# ESP-OLED.net
KiCad netlist of a schematic drawn in Altium Designer
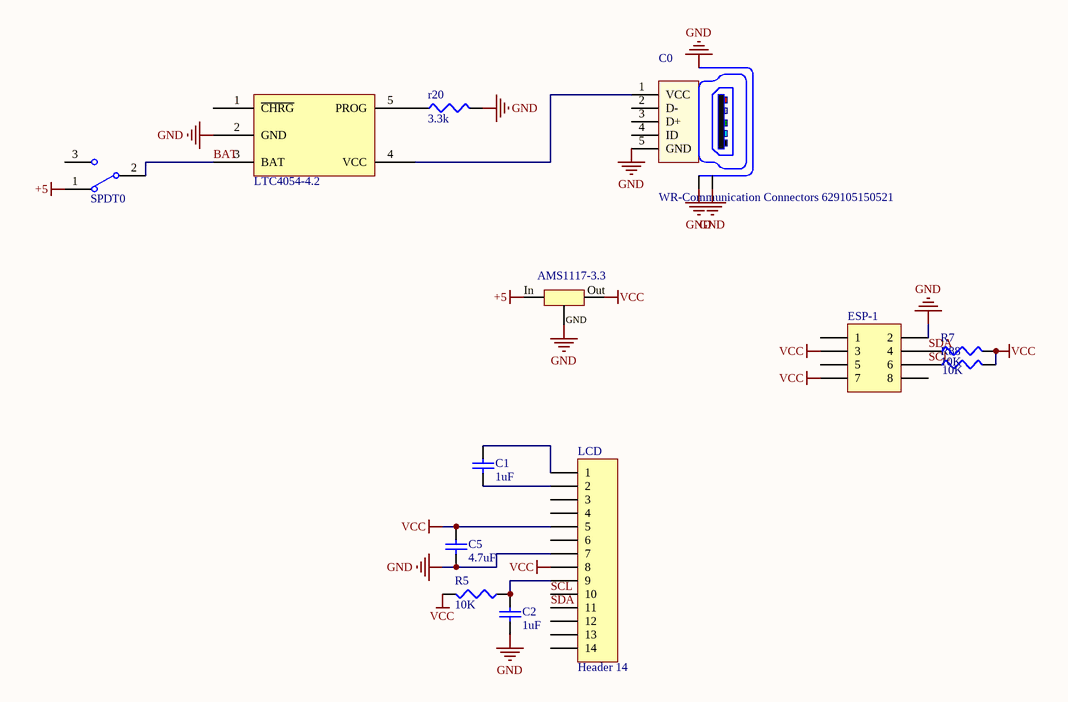
[diagram p0: ESP-OLED.SchDoc]

(export (version "E")
  (design (tool "Eeschema 10.0.6"))
  (components
    (comp (ref "ads") (value "LTC4054-4.2") (footprint "S5") (libsource (lib "arad") (part "LTC4054-4.2")))
    (comp (ref "C0")
      (value "WR-Communication Connectors 629105150521")
      (footprint "arad:629105150521_no_fixtures")
      (description "WR-COM_USB_Micro Type B_Horizontal_SMT")
      (fields
        (field (name "MANUFACTURER") "Würth Elektronik eiSos GmbH")
        (field (name "PARTNO") "629105150521")
        (field (name "CREATED BY") "Karrer Zheng")
      )
      (libsource (lib "arad") (part "WR-Communication Connectors 629105150521"))
    )
    (comp (ref "C1")
      (value "1uF")
      (footprint "1608[0603]")
      (description "Capacitor (Semiconductor SIM Model)")
      (fields (field (name "Comment") "Cap Semi") (field (name "PUBLISHER") "Altium Limited"))
      (libsource (lib "Miscellaneous Devices") (part "Cap Semi"))
    )
    (comp (ref "C2")
      (value "1uF")
      (footprint "1608[0603]")
      (description "Capacitor (Semiconductor SIM Model)")
      (fields (field (name "Comment") "Cap Semi") (field (name "PUBLISHER") "Altium Limited"))
      (libsource (lib "Miscellaneous Devices") (part "Cap Semi"))
    )
    (comp (ref "C5")
      (value "4.7uF")
      (footprint "1608[0603]")
      (description "Capacitor (Semiconductor SIM Model)")
      (fields (field (name "Comment") "Cap Semi") (field (name "PUBLISHER") "Altium Limited"))
      (libsource (lib "Miscellaneous Devices") (part "Cap Semi"))
    )
    (comp (ref "ESP-1")
      (value "Header 4X2")
      (footprint "ESP-01")
      (description "Header, 4-Pin, Dual row")
      (fields (field (name "PUBLISHER") "Altium Limited"))
      (libsource (lib "Miscellaneous Connectors") (part "Header 4X2"))
    )
    (comp (ref "LCD")
      (value "Header 14")
      (footprint "oled0.91")
      (description "Header, 14-Pin")
      (fields (field (name "PUBLISHER") "Altium Limited"))
      (libsource (lib "Miscellaneous Connectors") (part "Header 14"))
    )
    (comp (ref "R5")
      (value "10K")
      (footprint "J1-0603")
      (description "Resistor")
      (fields (field (name "Comment") "Res3") (field (name "PUBLISHER") "Altium Limited"))
      (libsource (lib "Miscellaneous Devices") (part "Res3"))
    )
    (comp (ref "R7")
      (value "10K")
      (footprint "J1-0603")
      (description "Resistor")
      (fields (field (name "Comment") "Res3") (field (name "PUBLISHER") "Altium Limited"))
      (libsource (lib "Miscellaneous Devices") (part "Res3"))
    )
    (comp (ref "r20")
      (value "3.3k")
      (footprint "J1-0603")
      (description "Resistor")
      (fields (field (name "Comment") "Res3") (field (name "PUBLISHER") "Altium Limited"))
      (libsource (lib "Miscellaneous Devices") (part "Res3"))
    )
    (comp (ref "R88")
      (value "10K")
      (footprint "J1-0603")
      (description "Resistor")
      (fields (field (name "Comment") "Res3") (field (name "PUBLISHER") "Altium Limited"))
      (libsource (lib "Miscellaneous Devices") (part "Res3"))
    )
    (comp (ref "reg")
      (value "AMS1117-3.3")
      (footprint "SOT223")
      (libsource (lib "Diverse") (part "AMS1117-3.3"))
    )
    (comp (ref "SPDT0")
      (value "450404015514")
      (footprint "450404015514")
      (description "WS-SLSU Mini SMT Slide Switch, Same Side Connection, Right Angled, SPDT")
      (fields (field (name "PUBLISHER") "Wurth Elektronik"))
      (libsource (lib "arad") (part "450404015514"))
    )
  )
  (nets
    (net (code "1") (name "+5") (class "Default")
      (node (ref "SPDT0") (pin "1") (pinfunction "1_1") (pintype "passive"))
      (node (ref "reg") (pin "3") (pinfunction "3_3") (pintype "passive"))
    )
    (net (code "2") (name "/BAT") (class "Default")
      (node (ref "SPDT0") (pin "2") (pinfunction "COM_2") (pintype "passive"))
      (node (ref "ads") (pin "3") (pinfunction "BAT_3") (pintype "passive"))
    )
    (net (code "3") (name "/SCL") (class "Default")
      (node (ref "ESP-1") (pin "6") (pinfunction "6_6") (pintype "passive"))
      (node (ref "LCD") (pin "10") (pinfunction "10_10") (pintype "passive"))
      (node (ref "R88") (pin "1") (pinfunction "1_1") (pintype "passive"))
    )
    (net (code "4") (name "/SDA") (class "Default")
      (node (ref "ESP-1") (pin "4") (pinfunction "4_4") (pintype "passive"))
      (node (ref "LCD") (pin "11") (pinfunction "11_11") (pintype "passive"))
      (node (ref "R7") (pin "1") (pinfunction "1_1") (pintype "passive"))
    )
    (net (code "5") (name "GND") (class "Default")
      (node (ref "C0") (pin "5") (pinfunction "GND_5") (pintype "passive"))
      (node (ref "C0") (pin "Z1") (pinfunction "Shield_Z1") (pintype "passive"))
      (node (ref "C0") (pin "Z2") (pinfunction "Shield_Z2") (pintype "passive"))
      (node (ref "C2") (pin "1") (pinfunction "1_1") (pintype "passive"))
      (node (ref "C5") (pin "1") (pinfunction "1_1") (pintype "passive"))
      (node (ref "ESP-1") (pin "2") (pinfunction "2_2") (pintype "passive"))
      (node (ref "LCD") (pin "7") (pinfunction "7_7") (pintype "passive"))
      (node (ref "ads") (pin "2") (pinfunction "GND_2") (pintype "passive"))
      (node (ref "r20") (pin "2") (pinfunction "2_2") (pintype "passive"))
      (node (ref "reg") (pin "1") (pinfunction "1_1") (pintype "passive"))
    )
    (net (code "6") (name "Net-(C0-VCC)") (class "Default")
      (node (ref "C0") (pin "1") (pinfunction "VCC_1") (pintype "passive"))
      (node (ref "ads") (pin "4") (pinfunction "VCC_4") (pintype "passive"))
    )
    (net (code "7") (name "Net-(C1-Pad1)") (class "Default")
      (node (ref "C1") (pin "1") (pinfunction "1_1") (pintype "passive"))
      (node (ref "LCD") (pin "2") (pinfunction "2_2") (pintype "passive"))
    )
    (net (code "8") (name "Net-(C1-Pad2)") (class "Default")
      (node (ref "C1") (pin "2") (pinfunction "2_2") (pintype "passive"))
      (node (ref "LCD") (pin "1") (pinfunction "1_1") (pintype "passive"))
    )
    (net (code "9") (name "Net-(C2-Pad2)") (class "Default")
      (node (ref "C2") (pin "2") (pinfunction "2_2") (pintype "passive"))
      (node (ref "LCD") (pin "9") (pinfunction "9_9") (pintype "passive"))
      (node (ref "R5") (pin "1") (pinfunction "1_1") (pintype "passive"))
    )
    (net (code "10") (name "Net-(ads-PROG)") (class "Default")
      (node (ref "ads") (pin "5") (pinfunction "PROG_5") (pintype "passive"))
      (node (ref "r20") (pin "1") (pinfunction "1_1") (pintype "passive"))
    )
    (net (code "11") (name "VCC") (class "Default")
      (node (ref "C5") (pin "2") (pinfunction "2_2") (pintype "passive"))
      (node (ref "ESP-1") (pin "3") (pinfunction "3_3") (pintype "passive"))
      (node (ref "ESP-1") (pin "7") (pinfunction "7_7") (pintype "passive"))
      (node (ref "LCD") (pin "5") (pinfunction "5_5") (pintype "passive"))
      (node (ref "LCD") (pin "8") (pinfunction "8_8") (pintype "passive"))
      (node (ref "R5") (pin "2") (pinfunction "2_2") (pintype "passive"))
      (node (ref "R7") (pin "2") (pinfunction "2_2") (pintype "passive"))
      (node (ref "R88") (pin "2") (pinfunction "2_2") (pintype "passive"))
      (node (ref "reg") (pin "2") (pinfunction "2_2") (pintype "passive"))
    )
    (net (code "12") (name "unconnected-(C0-D+-Pad3)") (class "Default")
      (node (ref "C0") (pin "3") (pinfunction "D+_3") (pintype "passive"))
    )
    (net (code "13") (name "unconnected-(C0-D--Pad2)") (class "Default")
      (node (ref "C0") (pin "2") (pinfunction "D-_2") (pintype "passive"))
    )
    (net (code "14") (name "unconnected-(C0-ID-Pad4)") (class "Default")
      (node (ref "C0") (pin "4") (pinfunction "ID_4") (pintype "passive"))
    )
    (net (code "15") (name "unconnected-(ESP-1-Pad1)") (class "Default")
      (node (ref "ESP-1") (pin "1") (pinfunction "1_1") (pintype "passive"))
    )
    (net (code "16") (name "unconnected-(ESP-1-Pad5)") (class "Default")
      (node (ref "ESP-1") (pin "5") (pinfunction "5_5") (pintype "passive"))
    )
    (net (code "17") (name "unconnected-(ESP-1-Pad8)") (class "Default")
      (node (ref "ESP-1") (pin "8") (pinfunction "8_8") (pintype "passive"))
    )
    (net (code "18") (name "unconnected-(LCD-Pad3)") (class "Default")
      (node (ref "LCD") (pin "3") (pinfunction "3_3") (pintype "passive"))
    )
    (net (code "19") (name "unconnected-(LCD-Pad4)") (class "Default")
      (node (ref "LCD") (pin "4") (pinfunction "4_4") (pintype "passive"))
    )
    (net (code "20") (name "unconnected-(LCD-Pad6)") (class "Default")
      (node (ref "LCD") (pin "6") (pinfunction "6_6") (pintype "passive"))
    )
    (net (code "21") (name "unconnected-(LCD-Pad12)") (class "Default")
      (node (ref "LCD") (pin "12") (pinfunction "12_12") (pintype "passive"))
    )
    (net (code "22") (name "unconnected-(LCD-Pad13)") (class "Default")
      (node (ref "LCD") (pin "13") (pinfunction "13_13") (pintype "passive"))
    )
    (net (code "23") (name "unconnected-(LCD-Pad14)") (class "Default")
      (node (ref "LCD") (pin "14") (pinfunction "14_14") (pintype "passive"))
    )
    (net (code "24") (name "unconnected-(SPDT0-Pad3)") (class "Default")
      (node (ref "SPDT0") (pin "3") (pinfunction "3_3") (pintype "passive"))
    )
    (net (code "25") (name "unconnected-(ads-~{CHRG}-Pad1)") (class "Default")
      (node (ref "ads") (pin "1") (pinfunction "~{CHRG}_1") (pintype "passive"))
    )
  )
)
